# Display.net
KiCad netlist of a schematic drawn in Altium Designer
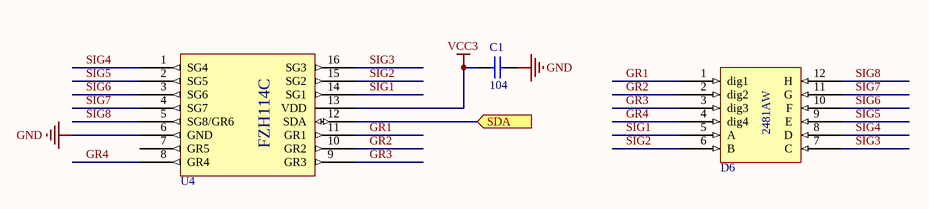
[diagram p0: Display.SchDoc]

(export (version "E")
  (design (tool "Eeschema 10.0.6"))
  (components
    (comp (ref "C1")
      (value "104")
      (description "Capacitor")
      (fields (field (name "Comment") "Cap") (field (name "PUBLISHER") "Altium Limited"))
      (libsource (lib "Miscellaneous Devices") (part "Cap"))
    )
    (comp (ref "D6") (value "D*") (libsource (lib "Schlib") (part "2481AW")))
    (comp (ref "U4") (value "FZ114") (libsource (lib "Schlib") (part "FZ114")))
  )
  (nets
    (net (code "1") (name "/GR1") (class "Default")
      (node (ref "D6") (pin "1") (pinfunction "dig1_1") (pintype "input"))
      (node (ref "U4") (pin "11") (pinfunction "GR1_11") (pintype "output"))
    )
    (net (code "2") (name "/GR2") (class "Default")
      (node (ref "D6") (pin "2") (pinfunction "dig2_2") (pintype "input"))
      (node (ref "U4") (pin "10") (pinfunction "GR2_10") (pintype "output"))
    )
    (net (code "3") (name "/GR3") (class "Default")
      (node (ref "D6") (pin "3") (pinfunction "dig3_3") (pintype "input"))
      (node (ref "U4") (pin "9") (pinfunction "GR3_9") (pintype "output"))
    )
    (net (code "4") (name "/GR4") (class "Default")
      (node (ref "D6") (pin "4") (pinfunction "dig4_4") (pintype "input"))
      (node (ref "U4") (pin "8") (pinfunction "GR4_8") (pintype "output"))
    )
    (net (code "5") (name "/SDA") (class "Default")
      (node (ref "U4") (pin "12") (pinfunction "SDA_12") (pintype "bidirectional"))
    )
    (net (code "6") (name "/SIG1") (class "Default")
      (node (ref "D6") (pin "5") (pinfunction "A_5") (pintype "input"))
      (node (ref "U4") (pin "14") (pinfunction "SG1_14") (pintype "output"))
    )
    (net (code "7") (name "/SIG2") (class "Default")
      (node (ref "D6") (pin "6") (pinfunction "B_6") (pintype "input"))
      (node (ref "U4") (pin "15") (pinfunction "SG2_15") (pintype "output"))
    )
    (net (code "8") (name "/SIG3") (class "Default")
      (node (ref "D6") (pin "7") (pinfunction "C_7") (pintype "input"))
      (node (ref "U4") (pin "16") (pinfunction "SG3_16") (pintype "output"))
    )
    (net (code "9") (name "/SIG4") (class "Default")
      (node (ref "D6") (pin "8") (pinfunction "D_8") (pintype "input"))
      (node (ref "U4") (pin "1") (pinfunction "SG4_1") (pintype "output"))
    )
    (net (code "10") (name "/SIG5") (class "Default")
      (node (ref "D6") (pin "9") (pinfunction "E_9") (pintype "input"))
      (node (ref "U4") (pin "2") (pinfunction "SG5_2") (pintype "output"))
    )
    (net (code "11") (name "/SIG6") (class "Default")
      (node (ref "D6") (pin "10") (pinfunction "F_10") (pintype "input"))
      (node (ref "U4") (pin "3") (pinfunction "SG6_3") (pintype "output"))
    )
    (net (code "12") (name "/SIG7") (class "Default")
      (node (ref "D6") (pin "11") (pinfunction "G_11") (pintype "input"))
      (node (ref "U4") (pin "4") (pinfunction "SG7_4") (pintype "output"))
    )
    (net (code "13") (name "/SIG8") (class "Default")
      (node (ref "D6") (pin "12") (pinfunction "H_12") (pintype "input"))
      (node (ref "U4") (pin "5") (pinfunction "SG8/GR6_5") (pintype "output"))
    )
    (net (code "14") (name "GND") (class "Default")
      (node (ref "C1") (pin "2") (pinfunction "2_2") (pintype "passive"))
      (node (ref "U4") (pin "6") (pinfunction "GND_6") (pintype "output"))
    )
    (net (code "15") (name "VCC3") (class "Default")
      (node (ref "C1") (pin "1") (pinfunction "1_1") (pintype "passive"))
      (node (ref "U4") (pin "13") (pinfunction "VDD_13") (pintype "power_in"))
    )
    (net (code "16") (name "unconnected-(U4-GR5-Pad7)") (class "Default")
      (node (ref "U4") (pin "7") (pinfunction "GR5_7") (pintype "output"))
    )
  )
)
